# BME280.net
KiCad netlist of a schematic drawn in Altium Designer
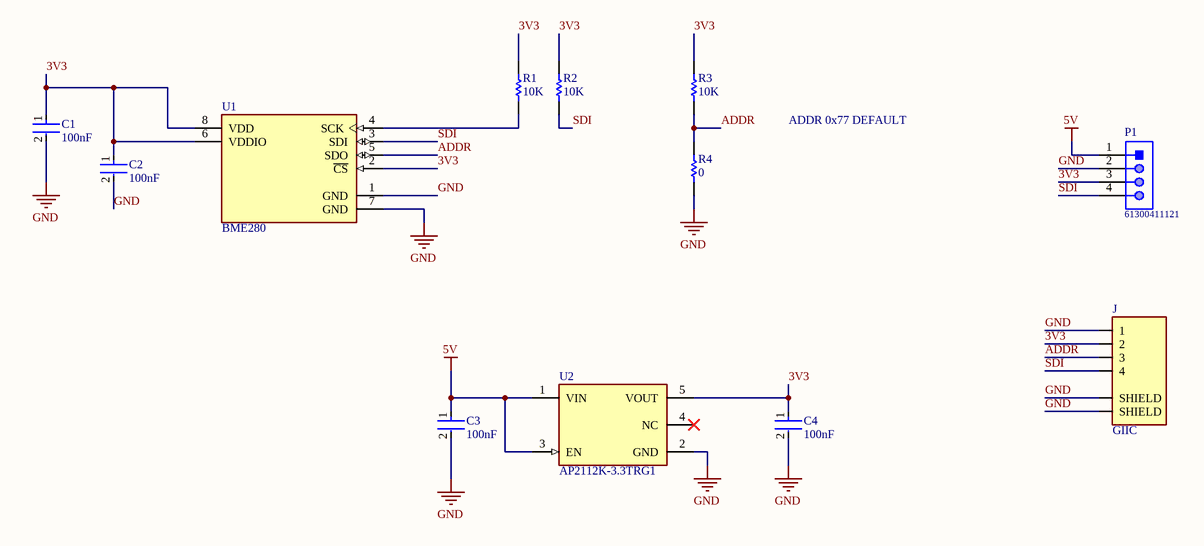
[diagram p0: BME280.SchDoc]

(export (version "E")
  (design (tool "Eeschema 10.0.6"))
  (components
    (comp (ref "C1")
      (value "100nF")
      (footprint "FP-C0805C-DN-MFG")
      (description "CAP CER 0.1UF 50V X7R 0805")
      (fields
        (field (name "MANUFACTURER PART NUMBER") "C0805C104K5RACTU")
        (field (name "MANUFACTURER") "KEMET")
      )
      (libsource (lib "Altium Content Vault") (part "b4654b650e69147ec39a6b967a45e02"))
    )
    (comp (ref "C2")
      (value "100nF")
      (footprint "FP-C0805C-DN-MFG")
      (description "CAP CER 0.1UF 50V X7R 0805")
      (fields
        (field (name "MANUFACTURER PART NUMBER") "C0805C104K5RACTU")
        (field (name "MANUFACTURER") "KEMET")
      )
      (libsource (lib "Altium Content Vault") (part "b4654b650e69147ec39a6b967a45e02"))
    )
    (comp (ref "C3")
      (value "100nF")
      (footprint "FP-C0805C-DN-MFG")
      (description "CAP CER 0.1UF 50V X7R 0805")
      (fields
        (field (name "MANUFACTURER PART NUMBER") "C0805C104K5RACTU")
        (field (name "MANUFACTURER") "KEMET")
      )
      (libsource (lib "Altium Content Vault") (part "b4654b650e69147ec39a6b967a45e02"))
    )
    (comp (ref "C4")
      (value "100nF")
      (footprint "FP-C0805C-DN-MFG")
      (description "CAP CER 0.1UF 50V X7R 0805")
      (fields
        (field (name "MANUFACTURER PART NUMBER") "C0805C104K5RACTU")
        (field (name "MANUFACTURER") "KEMET")
      )
      (libsource (lib "Altium Content Vault") (part "b4654b650e69147ec39a6b967a45e02"))
    )
    (comp (ref "J")
      (value "GIIC")
      (footprint "JST_SM04B-SRSS-TB(LF)(SN)")
      (description "Connector Header Surface Mount, Right Angle 4 position 0.039 _1.00mm_")
      (fields (field (name "MF") "JST Sales") (field (name "MP") "SM04B-SRSS-TB_LF__SN_"))
      (libsource (lib "Isidro_Library") (part "SM04B-SRSS-TB(LF)(SN)"))
    )
    (comp (ref "P1")
      (value "61300411121")
      (footprint "61300411121")
      (description "THT Vertical Pin Header WR-PHD, Pitch 2.54 mm, Single Row, 4 pins")
      (fields (field (name "MANUFACTURER") "Wurth Elektronik") (field (name "PUBLISHER") "WurthElektronik"))
      (libsource (lib "Altium Content Vault") (part "WE-CN-1P-M-R4"))
    )
    (comp (ref "R1")
      (value "10K")
      (footprint "RESC2013X60X40LL20T25_A")
      (fields (field (name "TOLERANCE") "0.1%") (field (name "MANUFACTURER") "Panasonic"))
      (libsource (lib "Altium Content Vault") (part "RES-2"))
    )
    (comp (ref "R2")
      (value "10K")
      (footprint "RESC2013X60X40LL20T25_A")
      (fields (field (name "TOLERANCE") "0.1%") (field (name "MANUFACTURER") "Panasonic"))
      (libsource (lib "Altium Content Vault") (part "RES-2"))
    )
    (comp (ref "R3")
      (value "10K")
      (footprint "RESC2013X60X40LL20T25_A")
      (fields (field (name "TOLERANCE") "0.1%") (field (name "MANUFACTURER") "Panasonic"))
      (libsource (lib "Altium Content Vault") (part "RES-2"))
    )
    (comp (ref "R4")
      (value "0")
      (footprint "RESC2013X60X40LL20T25_A")
      (fields (field (name "TOLERANCE") "0.1%") (field (name "MANUFACTURER") "Panasonic"))
      (libsource (lib "Altium Content Vault") (part "RES-2"))
    )
    (comp (ref "U1")
      (value "BME280")
      (footprint "FP-BME280-MFG")
      (description "SENSOR PRESSURE HUMIDITY TEMP")
      (libsource (lib "Altium Content Vault") (part "d58e2f6669bc67e6a2bc6a28610ca79"))
    )
    (comp (ref "U2")
      (value "AP2112K-3.3TRG1")
      (footprint "FP-SOT25-IPC_A")
      (description "IC REG LINEAR 3.3V 600MA SOT25")
      (libsource (lib "Altium Content Vault") (part "c8ab751aee5229183125ab046a11caa"))
    )
  )
  (nets
    (net (code "1") (name "/3V3") (class "Default")
      (node (ref "C1") (pin "1") (pinfunction "1_1") (pintype "passive"))
      (node (ref "C2") (pin "1") (pinfunction "1_1") (pintype "passive"))
      (node (ref "C4") (pin "1") (pinfunction "1_1") (pintype "passive"))
      (node (ref "J") (pin "2") (pinfunction "2_2") (pintype "passive"))
      (node (ref "P1") (pin "3") (pinfunction "3_3") (pintype "passive"))
      (node (ref "R1") (pin "2") (pinfunction "2_2") (pintype "passive"))
      (node (ref "R2") (pin "2") (pinfunction "2_2") (pintype "passive"))
      (node (ref "R3") (pin "2") (pinfunction "2_2") (pintype "passive"))
      (node (ref "U1") (pin "2") (pinfunction "~{CS}_2") (pintype "input"))
      (node (ref "U1") (pin "6") (pinfunction "VDDIO_6") (pintype "power_in"))
      (node (ref "U1") (pin "8") (pinfunction "VDD_8") (pintype "power_in"))
      (node (ref "U2") (pin "5") (pinfunction "VOUT_5") (pintype "power_in"))
    )
    (net (code "2") (name "/ADDR") (class "Default")
      (node (ref "J") (pin "3") (pinfunction "3_3") (pintype "passive"))
      (node (ref "R3") (pin "1") (pinfunction "1_1") (pintype "passive"))
      (node (ref "R4") (pin "2") (pinfunction "2_2") (pintype "passive"))
      (node (ref "U1") (pin "5") (pinfunction "SDO_5") (pintype "bidirectional"))
    )
    (net (code "3") (name "/SDI") (class "Default")
      (node (ref "J") (pin "4") (pinfunction "4_4") (pintype "passive"))
      (node (ref "P1") (pin "4") (pinfunction "4_4") (pintype "passive"))
      (node (ref "R2") (pin "1") (pinfunction "1_1") (pintype "passive"))
      (node (ref "U1") (pin "3") (pinfunction "SDI_3") (pintype "bidirectional"))
    )
    (net (code "4") (name "5V") (class "Default")
      (node (ref "C3") (pin "1") (pinfunction "1_1") (pintype "passive"))
      (node (ref "P1") (pin "1") (pinfunction "1_1") (pintype "passive"))
      (node (ref "U2") (pin "1") (pinfunction "VIN_1") (pintype "power_in"))
      (node (ref "U2") (pin "3") (pinfunction "EN_3") (pintype "input"))
    )
    (net (code "5") (name "GND") (class "Default")
      (node (ref "C1") (pin "2") (pinfunction "2_2") (pintype "passive"))
      (node (ref "C2") (pin "2") (pinfunction "2_2") (pintype "passive"))
      (node (ref "C3") (pin "2") (pinfunction "2_2") (pintype "passive"))
      (node (ref "C4") (pin "2") (pinfunction "2_2") (pintype "passive"))
      (node (ref "J") (pin "1") (pinfunction "1_1") (pintype "passive"))
      (node (ref "J") (pin "S1") (pinfunction "SHIELD_S1") (pintype "passive"))
      (node (ref "J") (pin "S2") (pinfunction "SHIELD_S2") (pintype "passive"))
      (node (ref "P1") (pin "2") (pinfunction "2_2") (pintype "passive"))
      (node (ref "R4") (pin "1") (pinfunction "1_1") (pintype "passive"))
      (node (ref "U1") (pin "1") (pinfunction "GND_1") (pintype "power_in"))
      (node (ref "U1") (pin "7") (pinfunction "GND_7") (pintype "power_in"))
      (node (ref "U2") (pin "2") (pinfunction "GND_2") (pintype "power_in"))
    )
    (net (code "6") (name "Net-(U1-SCK)") (class "Default")
      (node (ref "R1") (pin "1") (pinfunction "1_1") (pintype "passive"))
      (node (ref "U1") (pin "4") (pinfunction "SCK_4") (pintype "input"))
    )
    (net (code "7") (name "unconnected-(U2-NC-Pad4)") (class "Default")
      (node (ref "U2") (pin "4") (pinfunction "NC_4") (pintype "passive+no_connect"))
    )
  )
)
